# conn_sdcard.net
KiCad netlist of a schematic drawn in Altium Designer
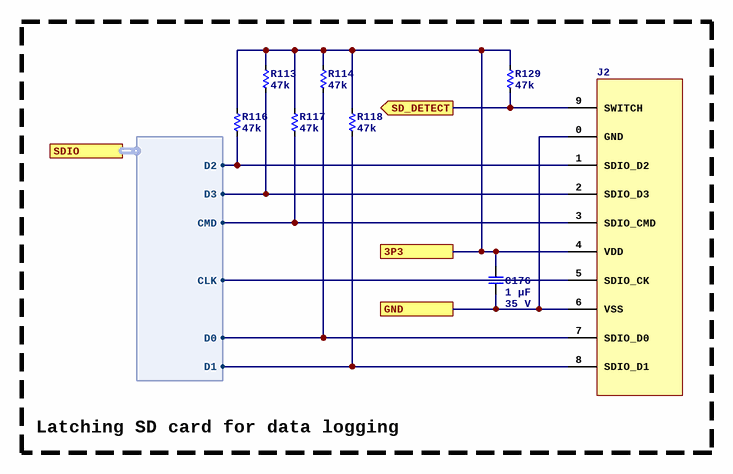
[diagram p0: conn_sdcard.SchDoc]

(export (version "E")
  (design (tool "Eeschema 10.0.6"))
  (components
    (comp (ref "C176")
      (value "GMK107AB7105KAHT")
      (footprint "C0603")
      (fields
        (field (name "CAPACITANCE") "1 µF")
        (field (name "MANUFACTURER") "Taiyo Yuden")
        (field (name "VOLTAGE RATING") "35 V")
      )
      (libsource (lib "database") (part "__template_cap"))
    )
    (comp (ref "J2")
      (value "DM3BT-DSF-PEJS")
      (footprint "HIROSE_DM3BT")
      (description "CONN MICRO SD R/A PUSH-PUSH SMD")
      (fields (field (name "MANUFACTURER") "Hirose Electric Co Ltd"))
      (libsource (lib "database") (part "DM3BT-DSF-PEJS"))
    )
    (comp (ref "R113")
      (value "47k")
      (footprint "R0402")
      (fields
        (field (name "TOLERANCE") "1%")
        (field (name "MANUFACTURER PART NUMBER") "0402WGF4702TCE")
        (field (name "MANUFACTURER") "UNI-ROYAL(Uniroyal Elec)")
      )
      (libsource (lib "database") (part "__template_resistor"))
    )
    (comp (ref "R114")
      (value "47k")
      (footprint "R0402")
      (fields
        (field (name "TOLERANCE") "1%")
        (field (name "MANUFACTURER PART NUMBER") "0402WGF4702TCE")
        (field (name "MANUFACTURER") "UNI-ROYAL(Uniroyal Elec)")
      )
      (libsource (lib "database") (part "__template_resistor"))
    )
    (comp (ref "R116")
      (value "47k")
      (footprint "R0402")
      (fields
        (field (name "TOLERANCE") "1%")
        (field (name "MANUFACTURER PART NUMBER") "0402WGF4702TCE")
        (field (name "MANUFACTURER") "UNI-ROYAL(Uniroyal Elec)")
      )
      (libsource (lib "database") (part "__template_resistor"))
    )
    (comp (ref "R117")
      (value "47k")
      (footprint "R0402")
      (fields
        (field (name "TOLERANCE") "1%")
        (field (name "MANUFACTURER PART NUMBER") "0402WGF4702TCE")
        (field (name "MANUFACTURER") "UNI-ROYAL(Uniroyal Elec)")
      )
      (libsource (lib "database") (part "__template_resistor"))
    )
    (comp (ref "R118")
      (value "47k")
      (footprint "R0402")
      (fields
        (field (name "TOLERANCE") "1%")
        (field (name "MANUFACTURER PART NUMBER") "0402WGF4702TCE")
        (field (name "MANUFACTURER") "UNI-ROYAL(Uniroyal Elec)")
      )
      (libsource (lib "database") (part "__template_resistor"))
    )
    (comp (ref "R129")
      (value "47k")
      (footprint "R0402")
      (fields
        (field (name "TOLERANCE") "1%")
        (field (name "MANUFACTURER PART NUMBER") "0402WGF4702TCE")
        (field (name "MANUFACTURER") "UNI-ROYAL(Uniroyal Elec)")
      )
      (libsource (lib "database") (part "__template_resistor"))
    )
  )
  (nets
    (net (code "2") (name "/3P3") (class "Default")
      (node (ref "C176") (pin "1") (pintype "passive"))
      (node (ref "J2") (pin "4") (pinfunction "VDD_4") (pintype "passive"))
      (node (ref "R113") (pin "2") (pintype "passive"))
      (node (ref "R114") (pin "2") (pintype "passive"))
      (node (ref "R116") (pin "2") (pintype "passive"))
      (node (ref "R117") (pin "2") (pintype "passive"))
      (node (ref "R118") (pin "2") (pintype "passive"))
      (node (ref "R129") (pin "2") (pintype "passive"))
    )
    (net (code "3") (name "/CLK") (class "Default")
      (node (ref "J2") (pin "5") (pinfunction "SDIO_CK_5") (pintype "passive"))
    )
    (net (code "4") (name "/CMD") (class "Default")
      (node (ref "J2") (pin "3") (pinfunction "SDIO_CMD_3") (pintype "passive"))
      (node (ref "R117") (pin "1") (pintype "passive"))
    )
    (net (code "5") (name "/D0") (class "Default")
      (node (ref "J2") (pin "7") (pinfunction "SDIO_D0_7") (pintype "passive"))
      (node (ref "R114") (pin "1") (pintype "passive"))
    )
    (net (code "6") (name "/D1") (class "Default")
      (node (ref "J2") (pin "8") (pinfunction "SDIO_D1_8") (pintype "passive"))
      (node (ref "R118") (pin "1") (pintype "passive"))
    )
    (net (code "7") (name "/D2") (class "Default")
      (node (ref "J2") (pin "1") (pinfunction "SDIO_D2_1") (pintype "passive"))
      (node (ref "R116") (pin "1") (pintype "passive"))
    )
    (net (code "8") (name "/D3") (class "Default")
      (node (ref "J2") (pin "2") (pinfunction "SDIO_D3_2") (pintype "passive"))
      (node (ref "R113") (pin "1") (pintype "passive"))
    )
    (net (code "9") (name "/GND") (class "Default")
      (node (ref "C176") (pin "2") (pintype "passive"))
      (node (ref "J2") (pin "0") (pinfunction "GND_0") (pintype "passive"))
      (node (ref "J2") (pin "6") (pinfunction "VSS_6") (pintype "passive"))
    )
    (net (code "10") (name "/SD_DETECT") (class "Default")
      (node (ref "J2") (pin "9") (pinfunction "SWITCH_9") (pintype "passive"))
      (node (ref "R129") (pin "1") (pintype "passive"))
    )
  )
)
